# schematic.net
KiCad netlist of a schematic drawn in EAGLE
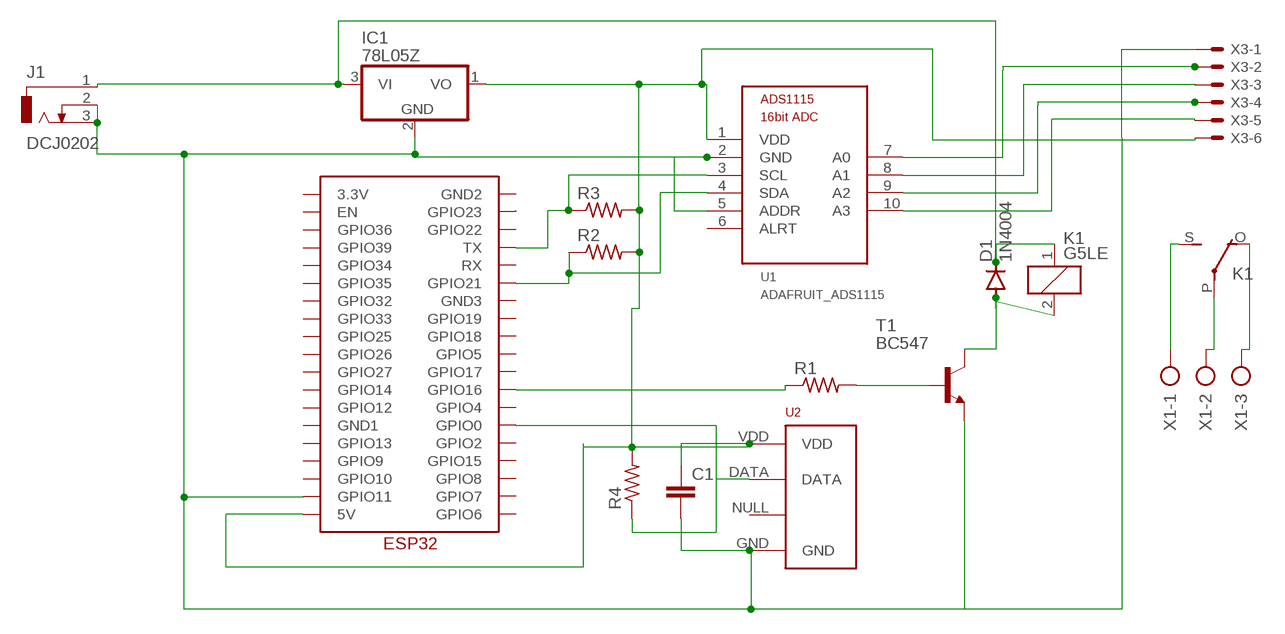
[diagram p0: schematic, sheet 1]

(export (version "E")
  (design (tool "Eeschema 10.0.6"))
  (components
    (comp (ref "C1")
      (value "C-EU025-025X050")
      (footprint "eagle-import:C025-025X050")
      (libsource (lib "eagle-import") (part "C-EU025-025X050"))
    )
    (comp (ref "D1")
      (value "1N4004")
      (footprint "eagle-import:DO41-10")
      (libsource (lib "eagle-import") (part "1N4004"))
    )
    (comp (ref "IC1")
      (value "78L05Z")
      (footprint "eagle-import:TO92")
      (libsource (lib "eagle-import") (part "78ZL05"))
    )
    (comp (ref "J1")
      (value "DCJ0202")
      (footprint "eagle-import:DCJ0202")
      (libsource (lib "eagle-import") (part "DCJ0202"))
    )
    (comp (ref "K1")
      (value "G5LE")
      (footprint "eagle-import:G5LE")
      (libsource (lib "eagle-import") (part "G5LE"))
    )
    (comp (ref "R1")
      (value "R-US_0309/12")
      (footprint "eagle-import:0309_12")
      (libsource (lib "eagle-import") (part "R-US_0309/12"))
    )
    (comp (ref "R2")
      (value "R-US_0309/12")
      (footprint "eagle-import:0309_12")
      (libsource (lib "eagle-import") (part "R-US_0309/12"))
    )
    (comp (ref "R3")
      (value "R-US_0309/12")
      (footprint "eagle-import:0309_12")
      (libsource (lib "eagle-import") (part "R-US_0309/12"))
    )
    (comp (ref "R4")
      (value "R-US_0309/12")
      (footprint "eagle-import:0309_12")
      (libsource (lib "eagle-import") (part "R-US_0309/12"))
    )
    (comp (ref "T1")
      (value "BC547")
      (footprint "eagle-import:TO92")
      (libsource (lib "eagle-import") (part "BC547"))
    )
    (comp (ref "U$1")
      (value "ESP32_GRBL")
      (footprint "eagle-import:ESP32_GRBL")
      (libsource (lib "eagle-import") (part "ESP32_GRBL"))
    )
    (comp (ref "U1")
      (value "ADAFRUIT_ADS1115")
      (footprint "eagle-import:ADAFRUIT_ADS1115_16BIT_I2C_ADC")
      (libsource (lib "eagle-import") (part "ADAFRUIT_ADS1115"))
    )
    (comp (ref "U2")
      (value "RHT03_DHT-22_AM2302RA")
      (footprint "eagle-import:RHT03_DHT-22_RA")
      (libsource (lib "eagle-import") (part "RHT03_DHT-22_AM2302RA"))
    )
    (comp (ref "X1")
      (value "AK300/3")
      (footprint "eagle-import:AK300_3")
      (libsource (lib "eagle-import") (part "AK300/3"))
    )
    (comp (ref "X3")
      (value "KK-156-6")
      (footprint "eagle-import:KK-156-6")
      (fields (field (name "MF") "MOLEX"))
      (libsource (lib "eagle-import") (part "KK-156-6"))
    )
  )
  (nets
    (net (code "1") (name "Net-(IC1-GND)") (class "Default")
      (node (ref "C1") (pin "2") (pinfunction "2_2") (pintype "passive"))
      (node (ref "IC1") (pin "2") (pinfunction "GND_2") (pintype "passive"))
      (node (ref "J1") (pin "2") (pinfunction "2_2") (pintype "passive"))
      (node (ref "J1") (pin "3") (pinfunction "3_3") (pintype "passive"))
      (node (ref "T1") (pin "1") (pinfunction "E_1") (pintype "passive"))
      (node (ref "U$1") (pin "GPIO11") (pinfunction "GPIO11_GPIO11") (pintype "bidirectional"))
      (node (ref "U1") (pin "2") (pinfunction "GND_2") (pintype "bidirectional"))
      (node (ref "U1") (pin "5") (pinfunction "ADDR_5") (pintype "bidirectional"))
      (node (ref "U2") (pin "GND") (pinfunction "GND_GND") (pintype "power_in"))
      (node (ref "X3") (pin "1") (pinfunction "S_1") (pintype "passive"))
    )
    (net (code "2") (name "Net-(IC1-VI)") (class "Default")
      (node (ref "D1") (pin "C") (pinfunction "C_C") (pintype "passive"))
      (node (ref "IC1") (pin "3") (pinfunction "VI_3") (pintype "input"))
      (node (ref "J1") (pin "1") (pinfunction "1_1") (pintype "passive"))
      (node (ref "K1") (pin "1") (pinfunction "1_1") (pintype "passive"))
    )
    (net (code "3") (name "Net-(IC1-VO)") (class "Default")
      (node (ref "C1") (pin "1") (pinfunction "1_1") (pintype "passive"))
      (node (ref "IC1") (pin "1") (pinfunction "VO_1") (pintype "passive"))
      (node (ref "R2") (pin "2") (pinfunction "2_2") (pintype "passive"))
      (node (ref "R3") (pin "2") (pinfunction "2_2") (pintype "passive"))
      (node (ref "R4") (pin "2") (pinfunction "2_2") (pintype "passive"))
      (node (ref "U$1") (pin "5V") (pinfunction "5V_5V") (pintype "bidirectional"))
      (node (ref "U1") (pin "1") (pinfunction "VDD_1") (pintype "bidirectional"))
      (node (ref "U2") (pin "VDD") (pinfunction "VDD_VDD") (pintype "power_in"))
      (node (ref "X3") (pin "6") (pinfunction "S_6") (pintype "passive"))
    )
    (net (code "4") (name "Net-(R1-Pad1)") (class "Default")
      (node (ref "R1") (pin "1") (pinfunction "1_1") (pintype "passive"))
      (node (ref "U$1") (pin "GPIO16") (pinfunction "GPIO16_GPIO16") (pintype "bidirectional"))
    )
    (net (code "5") (name "Net-(R4-Pad1)") (class "Default")
      (node (ref "R4") (pin "1") (pinfunction "1_1") (pintype "passive"))
      (node (ref "U$1") (pin "GPIO0") (pinfunction "GPIO0_GPIO0") (pintype "bidirectional"))
      (node (ref "U2") (pin "DATA") (pinfunction "DATA_DATA") (pintype "bidirectional"))
    )
    (net (code "6") (name "Net-(T1-B)") (class "Default")
      (node (ref "R1") (pin "2") (pinfunction "2_2") (pintype "passive"))
      (node (ref "T1") (pin "2") (pinfunction "B_2") (pintype "passive"))
    )
    (net (code "7") (name "Net-(T1-C)") (class "Default")
      (node (ref "D1") (pin "A") (pinfunction "A_A") (pintype "passive"))
      (node (ref "K1") (pin "2") (pinfunction "2_2") (pintype "passive"))
      (node (ref "T1") (pin "3") (pinfunction "C_3") (pintype "passive"))
    )
    (net (code "8") (name "Net-(U1-A0)") (class "Default")
      (node (ref "U1") (pin "7") (pinfunction "A0_7") (pintype "bidirectional"))
      (node (ref "X3") (pin "2") (pinfunction "S_2") (pintype "passive"))
    )
    (net (code "9") (name "Net-(U1-A1)") (class "Default")
      (node (ref "U1") (pin "8") (pinfunction "A1_8") (pintype "bidirectional"))
      (node (ref "X3") (pin "3") (pinfunction "S_3") (pintype "passive"))
    )
    (net (code "10") (name "Net-(U1-A2)") (class "Default")
      (node (ref "U1") (pin "9") (pinfunction "A2_9") (pintype "bidirectional"))
      (node (ref "X3") (pin "4") (pinfunction "S_4") (pintype "passive"))
    )
    (net (code "11") (name "Net-(U1-A3)") (class "Default")
      (node (ref "U1") (pin "10") (pinfunction "A3_10") (pintype "bidirectional"))
      (node (ref "X3") (pin "5") (pinfunction "S_5") (pintype "passive"))
    )
    (net (code "12") (name "Net-(U1-SCL)") (class "Default")
      (node (ref "R3") (pin "1") (pinfunction "1_1") (pintype "passive"))
      (node (ref "U$1") (pin "TX") (pinfunction "TX_TX") (pintype "bidirectional"))
      (node (ref "U1") (pin "3") (pinfunction "SCL_3") (pintype "bidirectional"))
    )
    (net (code "13") (name "Net-(U1-SDA)") (class "Default")
      (node (ref "R2") (pin "1") (pinfunction "1_1") (pintype "passive"))
      (node (ref "U$1") (pin "GPIO21") (pinfunction "GPIO21_GPIO21") (pintype "bidirectional"))
      (node (ref "U1") (pin "4") (pinfunction "SDA_4") (pintype "bidirectional"))
    )
    (net (code "14") (name "Net-(X1A-KL)") (class "Default")
      (node (ref "K1") (pin "S") (pinfunction "S_S") (pintype "passive"))
      (node (ref "X1") (pin "1") (pinfunction "KL_1") (pintype "passive"))
    )
    (net (code "15") (name "Net-(X1B-KL)") (class "Default")
      (node (ref "K1") (pin "P") (pinfunction "P_P") (pintype "passive"))
      (node (ref "X1") (pin "2") (pinfunction "KL_2") (pintype "passive"))
    )
    (net (code "16") (name "Net-(X1C-KL)") (class "Default")
      (node (ref "K1") (pin "O") (pinfunction "O_O") (pintype "passive"))
      (node (ref "X1") (pin "3") (pinfunction "KL_3") (pintype "passive"))
    )
    (net (code "17") (name "unconnected-(U$1-Pad3.3V)") (class "Default")
      (node (ref "U$1") (pin "3.3V") (pinfunction "3.3V_3.3V") (pintype "bidirectional"))
    )
    (net (code "18") (name "unconnected-(U$1-PadEN)") (class "Default")
      (node (ref "U$1") (pin "EN") (pinfunction "EN_EN") (pintype "bidirectional"))
    )
    (net (code "19") (name "unconnected-(U$1-PadGND1)") (class "Default")
      (node (ref "U$1") (pin "GND1") (pinfunction "GND1_GND1") (pintype "bidirectional"))
    )
    (net (code "20") (name "unconnected-(U$1-PadGND2)") (class "Default")
      (node (ref "U$1") (pin "GND2") (pinfunction "GND2_GND2") (pintype "bidirectional"))
    )
    (net (code "21") (name "unconnected-(U$1-PadGND3)") (class "Default")
      (node (ref "U$1") (pin "GND3") (pinfunction "GND3_GND3") (pintype "bidirectional"))
    )
    (net (code "22") (name "unconnected-(U$1-PadGPIO2)") (class "Default")
      (node (ref "U$1") (pin "GPIO2") (pinfunction "GPIO2_GPIO2") (pintype "bidirectional"))
    )
    (net (code "23") (name "unconnected-(U$1-PadGPIO4)") (class "Default")
      (node (ref "U$1") (pin "GPIO4") (pinfunction "GPIO4_GPIO4") (pintype "bidirectional"))
    )
    (net (code "24") (name "unconnected-(U$1-PadGPIO5)") (class "Default")
      (node (ref "U$1") (pin "GPIO5") (pinfunction "GPIO5_GPIO5") (pintype "bidirectional"))
    )
    (net (code "25") (name "unconnected-(U$1-PadGPIO6)") (class "Default")
      (node (ref "U$1") (pin "GPIO6") (pinfunction "GPIO6_GPIO6") (pintype "bidirectional"))
    )
    (net (code "26") (name "unconnected-(U$1-PadGPIO7)") (class "Default")
      (node (ref "U$1") (pin "GPIO7") (pinfunction "GPIO7_GPIO7") (pintype "bidirectional"))
    )
    (net (code "27") (name "unconnected-(U$1-PadGPIO8)") (class "Default")
      (node (ref "U$1") (pin "GPIO8") (pinfunction "GPIO8_GPIO8") (pintype "bidirectional"))
    )
    (net (code "28") (name "unconnected-(U$1-PadGPIO9)") (class "Default")
      (node (ref "U$1") (pin "GPIO9") (pinfunction "GPIO9_GPIO9") (pintype "bidirectional"))
    )
    (net (code "29") (name "unconnected-(U$1-PadGPIO10)") (class "Default")
      (node (ref "U$1") (pin "GPIO10") (pinfunction "GPIO10_GPIO10") (pintype "bidirectional"))
    )
    (net (code "30") (name "unconnected-(U$1-PadGPIO12)") (class "Default")
      (node (ref "U$1") (pin "GPIO12") (pinfunction "GPIO12_GPIO12") (pintype "bidirectional"))
    )
    (net (code "31") (name "unconnected-(U$1-PadGPIO13)") (class "Default")
      (node (ref "U$1") (pin "GPIO13") (pinfunction "GPIO13_GPIO13") (pintype "bidirectional"))
    )
    (net (code "32") (name "unconnected-(U$1-PadGPIO14)") (class "Default")
      (node (ref "U$1") (pin "GPIO14") (pinfunction "GPIO14_GPIO14") (pintype "bidirectional"))
    )
    (net (code "33") (name "unconnected-(U$1-PadGPIO15)") (class "Default")
      (node (ref "U$1") (pin "GPIO15") (pinfunction "GPIO15_GPIO15") (pintype "bidirectional"))
    )
    (net (code "34") (name "unconnected-(U$1-PadGPIO17)") (class "Default")
      (node (ref "U$1") (pin "GPIO17") (pinfunction "GPIO17_GPIO17") (pintype "bidirectional"))
    )
    (net (code "35") (name "unconnected-(U$1-PadGPIO18)") (class "Default")
      (node (ref "U$1") (pin "GPIO18") (pinfunction "GPIO18_GPIO18") (pintype "bidirectional"))
    )
    (net (code "36") (name "unconnected-(U$1-PadGPIO19)") (class "Default")
      (node (ref "U$1") (pin "GPIO19") (pinfunction "GPIO19_GPIO19") (pintype "bidirectional"))
    )
    (net (code "37") (name "unconnected-(U$1-PadGPIO22)") (class "Default")
      (node (ref "U$1") (pin "GPIO22") (pinfunction "GPIO22_GPIO22") (pintype "bidirectional"))
    )
    (net (code "38") (name "unconnected-(U$1-PadGPIO23)") (class "Default")
      (node (ref "U$1") (pin "GPIO23") (pinfunction "GPIO23_GPIO23") (pintype "bidirectional"))
    )
    (net (code "39") (name "unconnected-(U$1-PadGPIO25)") (class "Default")
      (node (ref "U$1") (pin "GPIO25") (pinfunction "GPIO25_GPIO25") (pintype "bidirectional"))
    )
    (net (code "40") (name "unconnected-(U$1-PadGPIO26)") (class "Default")
      (node (ref "U$1") (pin "GPIO26") (pinfunction "GPIO26_GPIO26") (pintype "bidirectional"))
    )
    (net (code "41") (name "unconnected-(U$1-PadGPIO27)") (class "Default")
      (node (ref "U$1") (pin "GPIO27") (pinfunction "GPIO27_GPIO27") (pintype "bidirectional"))
    )
    (net (code "42") (name "unconnected-(U$1-PadGPIO32)") (class "Default")
      (node (ref "U$1") (pin "GPIO32") (pinfunction "GPIO32_GPIO32") (pintype "bidirectional"))
    )
    (net (code "43") (name "unconnected-(U$1-PadGPIO33)") (class "Default")
      (node (ref "U$1") (pin "GPIO33") (pinfunction "GPIO33_GPIO33") (pintype "bidirectional"))
    )
    (net (code "44") (name "unconnected-(U$1-PadGPIO34)") (class "Default")
      (node (ref "U$1") (pin "GPIO34") (pinfunction "GPIO34_GPIO34") (pintype "bidirectional"))
    )
    (net (code "45") (name "unconnected-(U$1-PadGPIO35)") (class "Default")
      (node (ref "U$1") (pin "GPIO35") (pinfunction "GPIO35_GPIO35") (pintype "bidirectional"))
    )
    (net (code "46") (name "unconnected-(U$1-PadGPIO36)") (class "Default")
      (node (ref "U$1") (pin "GPIO36") (pinfunction "GPIO36_GPIO36") (pintype "bidirectional"))
    )
    (net (code "47") (name "unconnected-(U$1-PadGPIO39)") (class "Default")
      (node (ref "U$1") (pin "GPIO39") (pinfunction "GPIO39_GPIO39") (pintype "bidirectional"))
    )
    (net (code "48") (name "unconnected-(U$1-PadRX)") (class "Default")
      (node (ref "U$1") (pin "RX") (pinfunction "RX_RX") (pintype "bidirectional"))
    )
    (net (code "49") (name "unconnected-(U1-ALRT-Pad6)") (class "Default")
      (node (ref "U1") (pin "6") (pinfunction "ALRT_6") (pintype "bidirectional"))
    )
    (net (code "50") (name "unconnected-(U2-PadNULL)") (class "Default")
      (node (ref "U2") (pin "NULL") (pinfunction "NULL_NULL") (pintype "no_connect"))
    )
  )
)
